# RegisterInstruction.net
KiCad netlist of a schematic drawn in Altium Designer
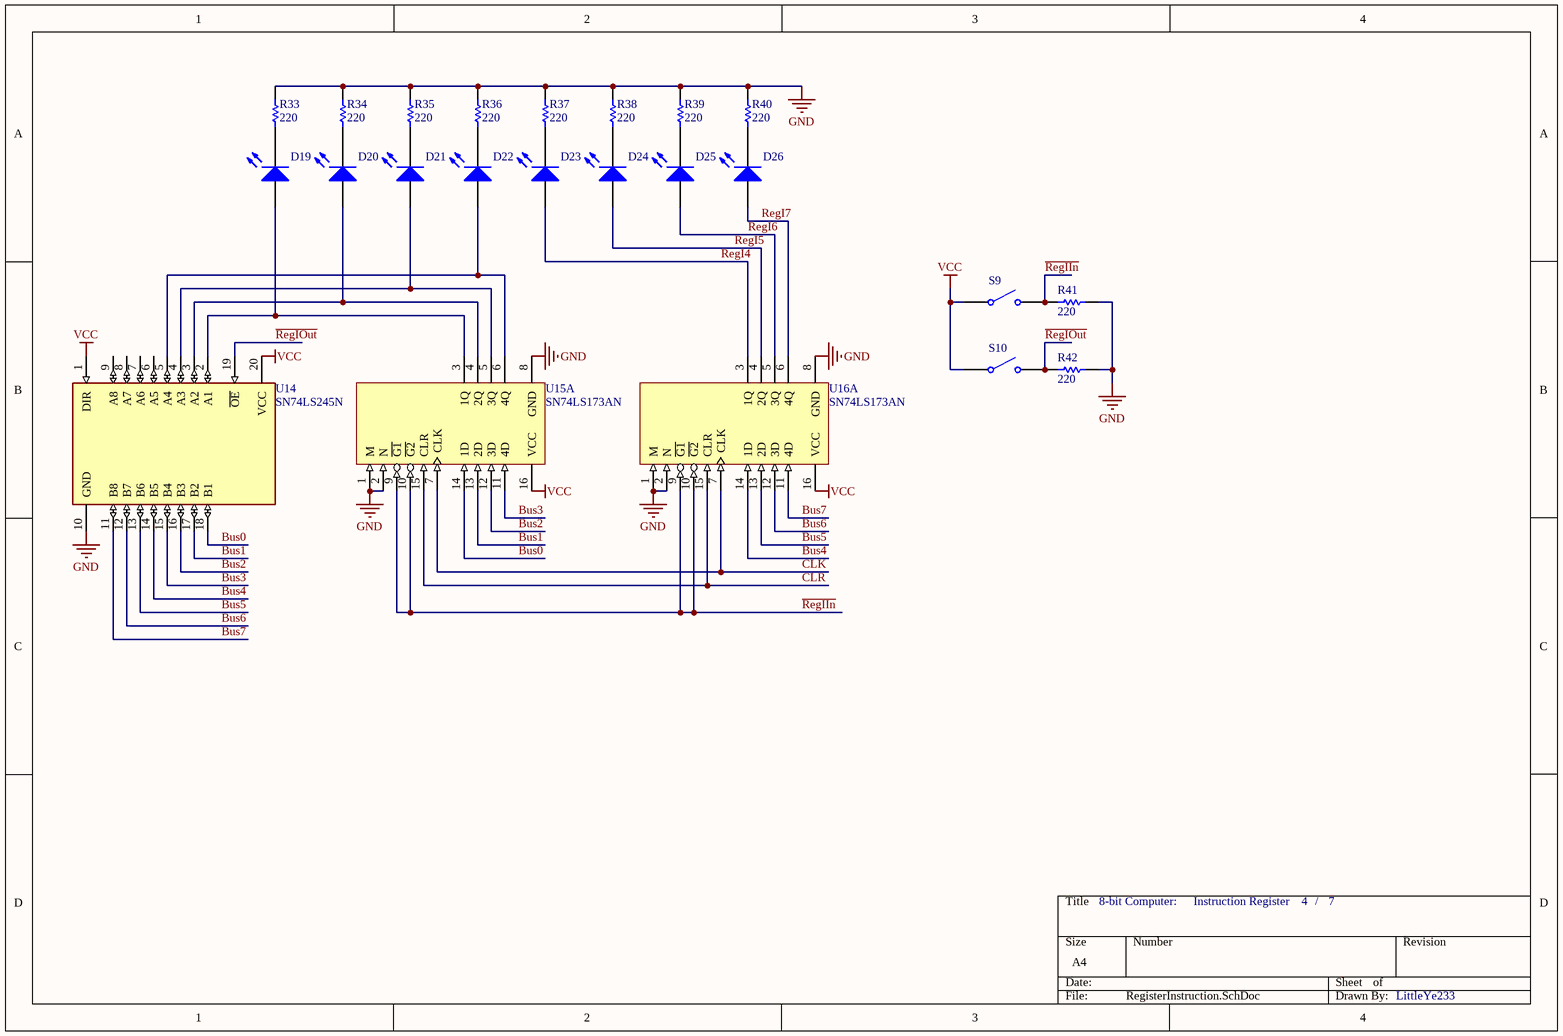
[diagram p0: RegisterInstruction.SchDoc]

(export (version "E")
  (design (tool "Eeschema 10.0.6"))
  (components
    (comp (ref "D19")
      (value "Light-Emitting Diode")
      (libsource (lib "Simulation Generic Components") (part "LED"))
    )
    (comp (ref "D20")
      (value "Light-Emitting Diode")
      (libsource (lib "Simulation Generic Components") (part "LED"))
    )
    (comp (ref "D21")
      (value "Light-Emitting Diode")
      (libsource (lib "Simulation Generic Components") (part "LED"))
    )
    (comp (ref "D22")
      (value "Light-Emitting Diode")
      (libsource (lib "Simulation Generic Components") (part "LED"))
    )
    (comp (ref "D23")
      (value "Light-Emitting Diode")
      (libsource (lib "Simulation Generic Components") (part "LED"))
    )
    (comp (ref "D24")
      (value "Light-Emitting Diode")
      (libsource (lib "Simulation Generic Components") (part "LED"))
    )
    (comp (ref "D25")
      (value "Light-Emitting Diode")
      (libsource (lib "Simulation Generic Components") (part "LED"))
    )
    (comp (ref "D26")
      (value "Light-Emitting Diode")
      (libsource (lib "Simulation Generic Components") (part "LED"))
    )
    (comp (ref "R33")
      (value "220")
      (description "Resistor")
      (libsource (lib "Simulation Generic Components") (part "Resistor"))
    )
    (comp (ref "R34")
      (value "220")
      (description "Resistor")
      (libsource (lib "Simulation Generic Components") (part "Resistor"))
    )
    (comp (ref "R35")
      (value "220")
      (description "Resistor")
      (libsource (lib "Simulation Generic Components") (part "Resistor"))
    )
    (comp (ref "R36")
      (value "220")
      (description "Resistor")
      (libsource (lib "Simulation Generic Components") (part "Resistor"))
    )
    (comp (ref "R37")
      (value "220")
      (description "Resistor")
      (libsource (lib "Simulation Generic Components") (part "Resistor"))
    )
    (comp (ref "R38")
      (value "220")
      (description "Resistor")
      (libsource (lib "Simulation Generic Components") (part "Resistor"))
    )
    (comp (ref "R39")
      (value "220")
      (description "Resistor")
      (libsource (lib "Simulation Generic Components") (part "Resistor"))
    )
    (comp (ref "R40")
      (value "220")
      (description "Resistor")
      (libsource (lib "Simulation Generic Components") (part "Resistor"))
    )
    (comp (ref "R41")
      (value "220")
      (description "Resistor")
      (libsource (lib "Simulation Generic Components") (part "Resistor"))
    )
    (comp (ref "R42")
      (value "220")
      (description "Resistor")
      (libsource (lib "Simulation Generic Components") (part "Resistor"))
    )
    (comp (ref "S9")
      (value "Single-Pole, Single-Throw Switch")
      (libsource (lib "Simulation Generic Components") (part "SPST SW"))
    )
    (comp (ref "S10")
      (value "Single-Pole, Single-Throw Switch")
      (libsource (lib "Simulation Generic Components") (part "SPST SW"))
    )
    (comp (ref "U14")
      (value "SN74LS245N")
      (footprint "FP-N0020A-MFG")
      (description "IC TXRX NON-INVERT 5.25V 20DIP")
      (libsource (lib "SN74LS245N") (part "CMP-1620-00419-3"))
    )
    (comp (ref "U15")
      (value "SN74LS173AN")
      (footprint "N0016A")
      (description "4-Bit D-type Registers with 3-State Outputs, N0016A, TUBE")
      (fields
        (field (name "MANUFACTURER") "Texas Instruments")
        (field (name "GENERIC PART NUMBER") "SN74LS173A")
      )
      (libsource (lib "SN74LS173AN") (part "CMP-1619-00777-2"))
    )
    (comp (ref "U16")
      (value "SN74LS173AN")
      (footprint "N0016A")
      (description "4-Bit D-type Registers with 3-State Outputs, N0016A, TUBE")
      (fields
        (field (name "MANUFACTURER") "Texas Instruments")
        (field (name "GENERIC PART NUMBER") "SN74LS173A")
      )
      (libsource (lib "SN74LS173AN") (part "CMP-1619-00777-2"))
    )
  )
  (nets
    (net (code "1") (name "/Bus0") (class "Default")
      (node (ref "U14") (pin "18") (pinfunction "B1_18") (pintype "bidirectional"))
      (node (ref "U15") (pin "14") (pinfunction "1D_14") (pintype "input"))
    )
    (net (code "2") (name "/Bus1") (class "Default")
      (node (ref "U14") (pin "17") (pinfunction "B2_17") (pintype "bidirectional"))
      (node (ref "U15") (pin "13") (pinfunction "2D_13") (pintype "input"))
    )
    (net (code "3") (name "/Bus2") (class "Default")
      (node (ref "U14") (pin "16") (pinfunction "B3_16") (pintype "bidirectional"))
      (node (ref "U15") (pin "12") (pinfunction "3D_12") (pintype "input"))
    )
    (net (code "4") (name "/Bus3") (class "Default")
      (node (ref "U14") (pin "15") (pinfunction "B4_15") (pintype "bidirectional"))
      (node (ref "U15") (pin "11") (pinfunction "4D_11") (pintype "input"))
    )
    (net (code "5") (name "/Bus4") (class "Default")
      (node (ref "U14") (pin "14") (pinfunction "B5_14") (pintype "bidirectional"))
      (node (ref "U16") (pin "14") (pinfunction "1D_14") (pintype "input"))
    )
    (net (code "6") (name "/Bus5") (class "Default")
      (node (ref "U14") (pin "13") (pinfunction "B6_13") (pintype "bidirectional"))
      (node (ref "U16") (pin "13") (pinfunction "2D_13") (pintype "input"))
    )
    (net (code "7") (name "/Bus6") (class "Default")
      (node (ref "U14") (pin "12") (pinfunction "B7_12") (pintype "bidirectional"))
      (node (ref "U16") (pin "12") (pinfunction "3D_12") (pintype "input"))
    )
    (net (code "8") (name "/Bus7") (class "Default")
      (node (ref "U14") (pin "11") (pinfunction "B8_11") (pintype "bidirectional"))
      (node (ref "U16") (pin "11") (pinfunction "4D_11") (pintype "input"))
    )
    (net (code "9") (name "/CLK") (class "Default")
      (node (ref "U15") (pin "7") (pinfunction "CLK_7") (pintype "input"))
      (node (ref "U16") (pin "7") (pinfunction "CLK_7") (pintype "input"))
    )
    (net (code "10") (name "/CLR") (class "Default")
      (node (ref "U15") (pin "15") (pinfunction "CLR_15") (pintype "input"))
      (node (ref "U16") (pin "15") (pinfunction "CLR_15") (pintype "input"))
    )
    (net (code "11") (name "/RegI4") (class "Default")
      (node (ref "D23") (pin "1") (pinfunction "A_1") (pintype "passive"))
      (node (ref "U16") (pin "3") (pinfunction "1Q_3") (pintype "tri_state"))
    )
    (net (code "12") (name "/RegI5") (class "Default")
      (node (ref "D24") (pin "1") (pinfunction "A_1") (pintype "passive"))
      (node (ref "U16") (pin "4") (pinfunction "2Q_4") (pintype "tri_state"))
    )
    (net (code "13") (name "/RegI6") (class "Default")
      (node (ref "D25") (pin "1") (pinfunction "A_1") (pintype "passive"))
      (node (ref "U16") (pin "5") (pinfunction "3Q_5") (pintype "tri_state"))
    )
    (net (code "14") (name "/RegI7") (class "Default")
      (node (ref "D26") (pin "1") (pinfunction "A_1") (pintype "passive"))
      (node (ref "U16") (pin "6") (pinfunction "4Q_6") (pintype "tri_state"))
    )
    (net (code "15") (name "/~{RegIIn}") (class "Default")
      (node (ref "R41") (pin "2") (pinfunction "2_2") (pintype "passive"))
      (node (ref "S9") (pin "2") (pinfunction "2_2") (pintype "passive"))
      (node (ref "U15") (pin "10") (pinfunction "~{G2}_10") (pintype "input"))
      (node (ref "U15") (pin "9") (pinfunction "~{G1}_9") (pintype "input"))
      (node (ref "U16") (pin "10") (pinfunction "~{G2}_10") (pintype "input"))
      (node (ref "U16") (pin "9") (pinfunction "~{G1}_9") (pintype "input"))
    )
    (net (code "16") (name "/~{RegIOut}") (class "Default")
      (node (ref "R42") (pin "2") (pinfunction "2_2") (pintype "passive"))
      (node (ref "S10") (pin "2") (pinfunction "2_2") (pintype "passive"))
      (node (ref "U14") (pin "19") (pinfunction "~{OE}_19") (pintype "input"))
    )
    (net (code "17") (name "GND") (class "Default")
      (node (ref "R33") (pin "2") (pinfunction "2_2") (pintype "passive"))
      (node (ref "R34") (pin "2") (pinfunction "2_2") (pintype "passive"))
      (node (ref "R35") (pin "2") (pinfunction "2_2") (pintype "passive"))
      (node (ref "R36") (pin "2") (pinfunction "2_2") (pintype "passive"))
      (node (ref "R37") (pin "2") (pinfunction "2_2") (pintype "passive"))
      (node (ref "R38") (pin "2") (pinfunction "2_2") (pintype "passive"))
      (node (ref "R39") (pin "2") (pinfunction "2_2") (pintype "passive"))
      (node (ref "R40") (pin "2") (pinfunction "2_2") (pintype "passive"))
      (node (ref "R41") (pin "1") (pinfunction "1_1") (pintype "passive"))
      (node (ref "R42") (pin "1") (pinfunction "1_1") (pintype "passive"))
      (node (ref "U14") (pin "10") (pinfunction "GND_10") (pintype "power_in"))
      (node (ref "U15") (pin "1") (pinfunction "M_1") (pintype "input"))
      (node (ref "U15") (pin "2") (pinfunction "N_2") (pintype "input"))
      (node (ref "U15") (pin "8") (pinfunction "GND_8") (pintype "power_in"))
      (node (ref "U16") (pin "1") (pinfunction "M_1") (pintype "input"))
      (node (ref "U16") (pin "2") (pinfunction "N_2") (pintype "input"))
      (node (ref "U16") (pin "8") (pinfunction "GND_8") (pintype "power_in"))
    )
    (net (code "18") (name "Net-(D19-A)") (class "Default")
      (node (ref "D19") (pin "1") (pinfunction "A_1") (pintype "passive"))
      (node (ref "U14") (pin "2") (pinfunction "A1_2") (pintype "bidirectional"))
      (node (ref "U15") (pin "3") (pinfunction "1Q_3") (pintype "tri_state"))
    )
    (net (code "19") (name "Net-(D19-K)") (class "Default")
      (node (ref "D19") (pin "2") (pinfunction "K_2") (pintype "passive"))
      (node (ref "R33") (pin "1") (pinfunction "1_1") (pintype "passive"))
    )
    (net (code "20") (name "Net-(D20-A)") (class "Default")
      (node (ref "D20") (pin "1") (pinfunction "A_1") (pintype "passive"))
      (node (ref "U14") (pin "3") (pinfunction "A2_3") (pintype "bidirectional"))
      (node (ref "U15") (pin "4") (pinfunction "2Q_4") (pintype "tri_state"))
    )
    (net (code "21") (name "Net-(D20-K)") (class "Default")
      (node (ref "D20") (pin "2") (pinfunction "K_2") (pintype "passive"))
      (node (ref "R34") (pin "1") (pinfunction "1_1") (pintype "passive"))
    )
    (net (code "22") (name "Net-(D21-A)") (class "Default")
      (node (ref "D21") (pin "1") (pinfunction "A_1") (pintype "passive"))
      (node (ref "U14") (pin "4") (pinfunction "A3_4") (pintype "bidirectional"))
      (node (ref "U15") (pin "5") (pinfunction "3Q_5") (pintype "tri_state"))
    )
    (net (code "23") (name "Net-(D21-K)") (class "Default")
      (node (ref "D21") (pin "2") (pinfunction "K_2") (pintype "passive"))
      (node (ref "R35") (pin "1") (pinfunction "1_1") (pintype "passive"))
    )
    (net (code "24") (name "Net-(D22-A)") (class "Default")
      (node (ref "D22") (pin "1") (pinfunction "A_1") (pintype "passive"))
      (node (ref "U14") (pin "5") (pinfunction "A4_5") (pintype "bidirectional"))
      (node (ref "U15") (pin "6") (pinfunction "4Q_6") (pintype "tri_state"))
    )
    (net (code "25") (name "Net-(D22-K)") (class "Default")
      (node (ref "D22") (pin "2") (pinfunction "K_2") (pintype "passive"))
      (node (ref "R36") (pin "1") (pinfunction "1_1") (pintype "passive"))
    )
    (net (code "26") (name "Net-(D23-K)") (class "Default")
      (node (ref "D23") (pin "2") (pinfunction "K_2") (pintype "passive"))
      (node (ref "R37") (pin "1") (pinfunction "1_1") (pintype "passive"))
    )
    (net (code "27") (name "Net-(D24-K)") (class "Default")
      (node (ref "D24") (pin "2") (pinfunction "K_2") (pintype "passive"))
      (node (ref "R38") (pin "1") (pinfunction "1_1") (pintype "passive"))
    )
    (net (code "28") (name "Net-(D25-K)") (class "Default")
      (node (ref "D25") (pin "2") (pinfunction "K_2") (pintype "passive"))
      (node (ref "R39") (pin "1") (pinfunction "1_1") (pintype "passive"))
    )
    (net (code "29") (name "Net-(D26-K)") (class "Default")
      (node (ref "D26") (pin "2") (pinfunction "K_2") (pintype "passive"))
      (node (ref "R40") (pin "1") (pinfunction "1_1") (pintype "passive"))
    )
    (net (code "30") (name "VCC") (class "Default")
      (node (ref "S10") (pin "1") (pinfunction "1_1") (pintype "passive"))
      (node (ref "S9") (pin "1") (pinfunction "1_1") (pintype "passive"))
      (node (ref "U14") (pin "1") (pinfunction "DIR_1") (pintype "input"))
      (node (ref "U14") (pin "20") (pinfunction "VCC_20") (pintype "power_in"))
      (node (ref "U15") (pin "16") (pinfunction "VCC_16") (pintype "power_in"))
      (node (ref "U16") (pin "16") (pinfunction "VCC_16") (pintype "power_in"))
    )
    (net (code "31") (name "unconnected-(U14-A5-Pad6)") (class "Default")
      (node (ref "U14") (pin "6") (pinfunction "A5_6") (pintype "bidirectional"))
    )
    (net (code "32") (name "unconnected-(U14-A6-Pad7)") (class "Default")
      (node (ref "U14") (pin "7") (pinfunction "A6_7") (pintype "bidirectional"))
    )
    (net (code "33") (name "unconnected-(U14-A7-Pad8)") (class "Default")
      (node (ref "U14") (pin "8") (pinfunction "A7_8") (pintype "bidirectional"))
    )
    (net (code "34") (name "unconnected-(U14-A8-Pad9)") (class "Default")
      (node (ref "U14") (pin "9") (pinfunction "A8_9") (pintype "bidirectional"))
    )
  )
)
